# Sound.net
KiCad netlist of a schematic drawn in Altium Designer
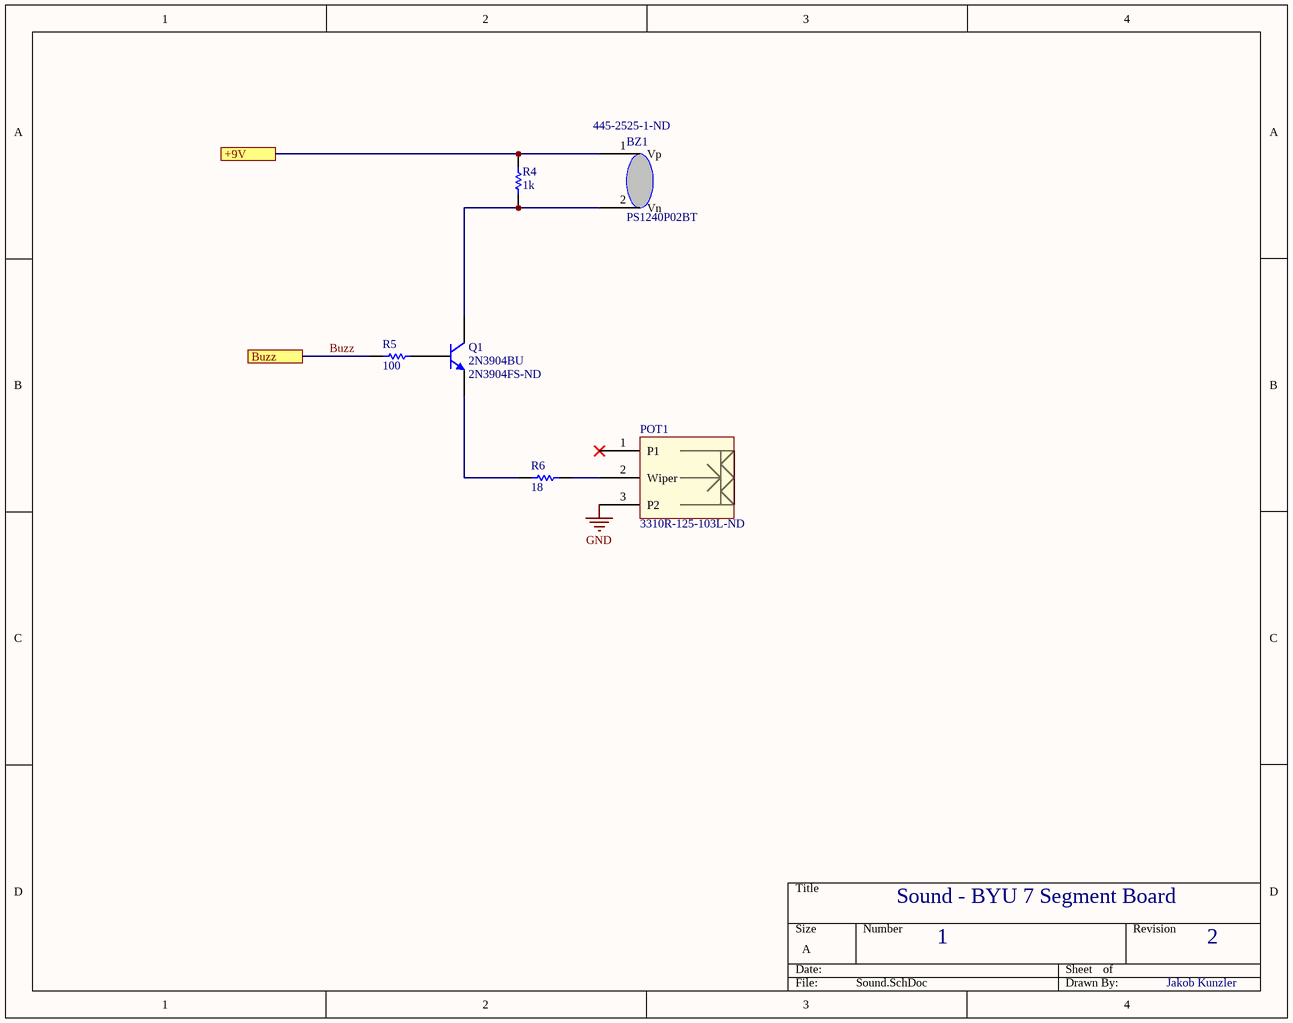
[diagram p0: Sound.SchDoc]

(export (version "E")
  (design (tool "Eeschema 10.0.6"))
  (components
    (comp (ref "BZ1")
      (value "PS1240P02BT")
      (footprint "PS1240P02BT")
      (description "Piezo Buzzer, Through Hole")
      (fields (field (name "SUPPLIER PART NUMBER 1") "445-2525-1-ND"))
      (libsource (lib "BYU7SegBoard") (part "PS12"))
    )
    (comp (ref "POT1")
      (value "3310R-125-103L")
      (footprint "3310R-001")
      (description "POT 10K OHM 1/4W PLASTIC LINEAR")
      (fields (field (name "SUPPLIER PART NUMBER 1") "3310R-125-103L-ND"))
      (libsource (lib "BYU7SegBoard") (part "Potentiometer - 10k"))
    )
    (comp (ref "Q1")
      (value "2N3904BU")
      (footprint "2N3904")
      (description "TRANS NPN 40V 0.2A TO-92")
      (fields
        (field (name "SUPPLIER PART NUMBER 1") "2N3904FS-ND")
        (field (name "PUBLISHER") "Altium Limited")
      )
      (libsource (lib "BYU7SegBoard") (part "2N3904"))
    )
    (comp (ref "R4")
      (value "1k")
      (footprint "Resistor Through Hole")
      (description "CF14JT1K00")
      (libsource (lib "BYU7SegBoard") (part "Resistor_1k"))
    )
    (comp (ref "R5")
      (value "100")
      (footprint "Resistor Through Hole")
      (description "CF14JT100R")
      (libsource (lib "BYU7SegBoard") (part "Resistor_100"))
    )
    (comp (ref "R6")
      (value "18")
      (footprint "Resistor Through Hole")
      (description "CF14JT18R0")
      (libsource (lib "BYU7SegBoard") (part "Resistor_18"))
    )
  )
  (nets
    (net (code "1") (name "/+9V") (class "Default")
      (node (ref "BZ1") (pin "1") (pinfunction "Vp_1") (pintype "passive"))
      (node (ref "R4") (pin "1") (pinfunction "1_1") (pintype "passive"))
    )
    (net (code "2") (name "/Buzz") (class "Default")
      (node (ref "R5") (pin "2") (pinfunction "2_2") (pintype "passive"))
    )
    (net (code "3") (name "GND") (class "Default")
      (node (ref "POT1") (pin "3") (pinfunction "P2_3") (pintype "passive"))
    )
    (net (code "4") (name "Net-(BZ1-Vn)") (class "Default")
      (node (ref "BZ1") (pin "2") (pinfunction "Vn_2") (pintype "passive"))
      (node (ref "Q1") (pin "3") (pinfunction "C_3") (pintype "passive"))
      (node (ref "R4") (pin "2") (pinfunction "2_2") (pintype "passive"))
    )
    (net (code "5") (name "Net-(POT1-Wiper)") (class "Default")
      (node (ref "POT1") (pin "2") (pinfunction "Wiper_2") (pintype "passive"))
      (node (ref "R6") (pin "1") (pinfunction "1_1") (pintype "passive"))
    )
    (net (code "6") (name "Net-(Q1-B)") (class "Default")
      (node (ref "Q1") (pin "2") (pinfunction "B_2") (pintype "passive"))
      (node (ref "R5") (pin "1") (pinfunction "1_1") (pintype "passive"))
    )
    (net (code "7") (name "Net-(Q1-E)") (class "Default")
      (node (ref "Q1") (pin "1") (pinfunction "E_1") (pintype "passive"))
      (node (ref "R6") (pin "2") (pinfunction "2_2") (pintype "passive"))
    )
    (net (code "8") (name "unconnected-(POT1-P1-Pad1)") (class "Default")
      (node (ref "POT1") (pin "1") (pinfunction "P1_1") (pintype "passive+no_connect"))
    )
  )
)
